# voltage_conditioning.net
KiCad netlist of a schematic drawn in Altium Designer
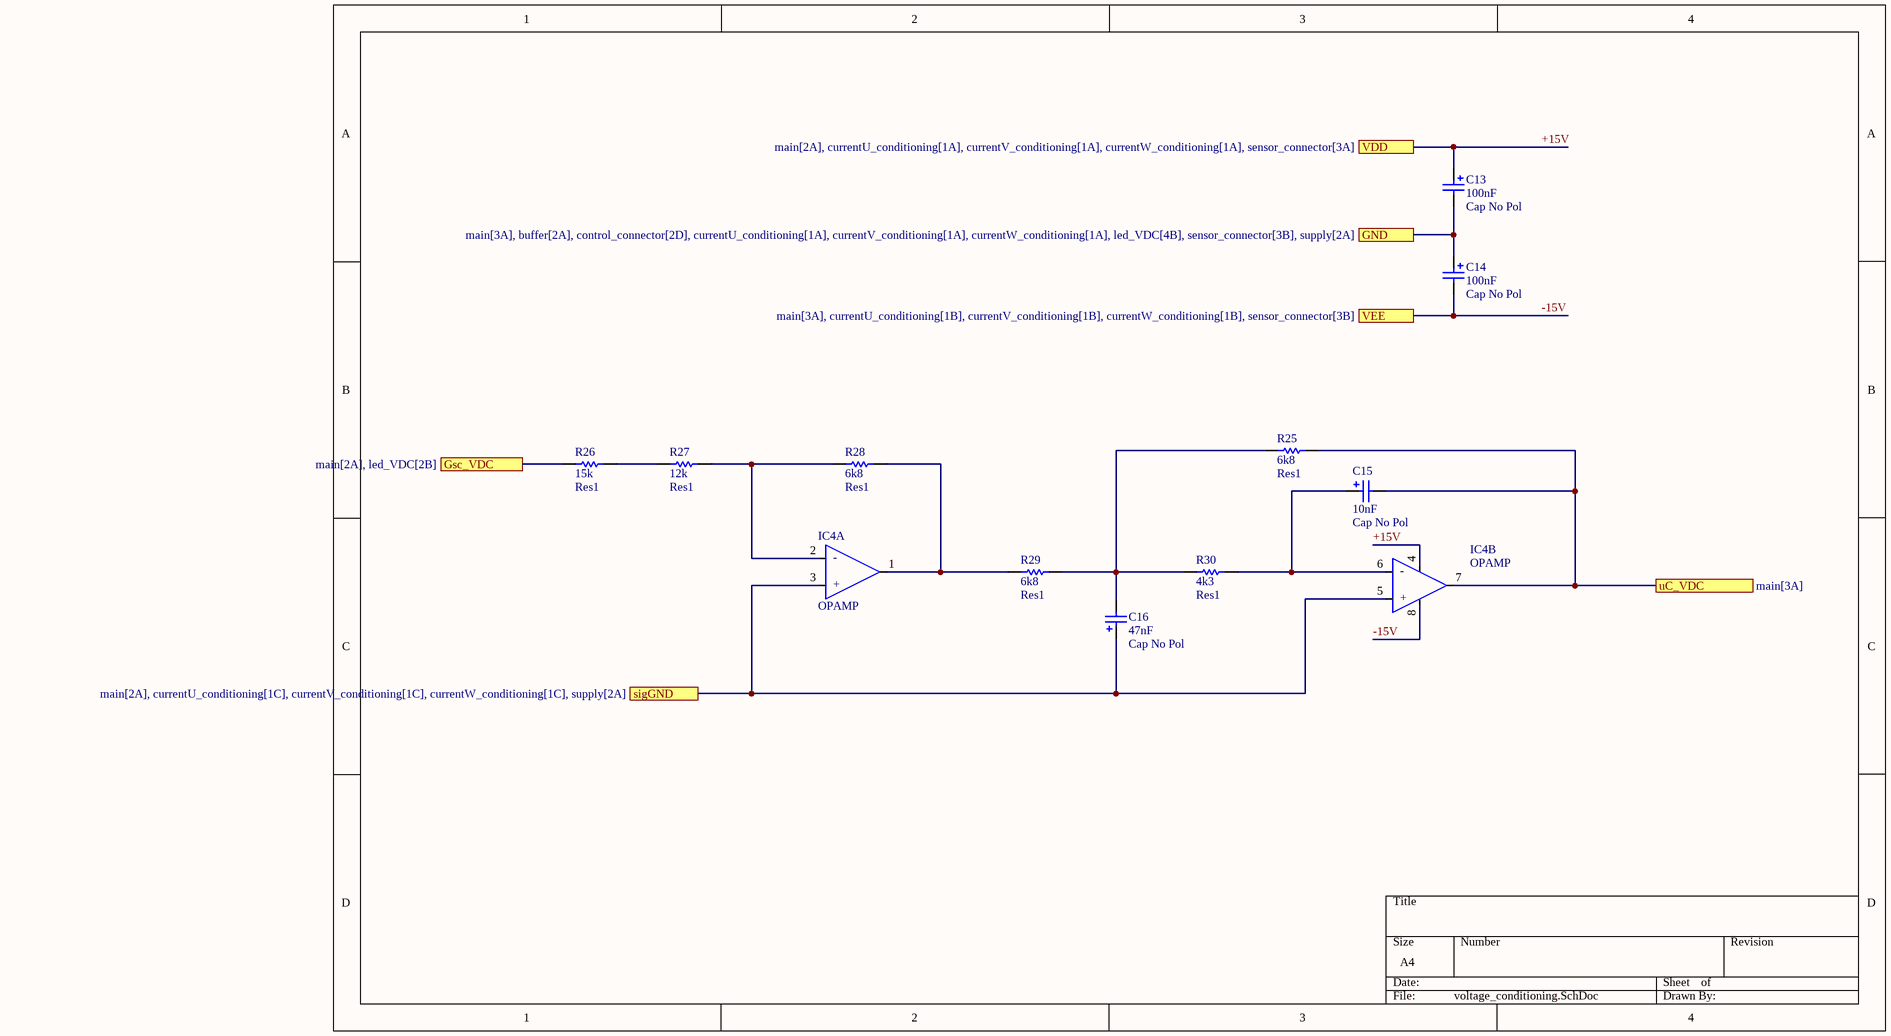
[diagram p0: voltage_conditioning.SchDoc]

(export (version "E")
  (design (tool "Eeschema 10.0.6"))
  (components
    (comp (ref "C13")
      (value "Cap No Pol")
      (footprint "RAD-0.1")
      (description "Polarized Capacitor (Radial)")
      (fields (field (name "ALTIUM_VALUE") "100nF") (field (name "PUBLISHER") "Altium Limited"))
      (libsource (lib "LABSTEPS_Project") (part "Cap No Pol"))
    )
    (comp (ref "C14")
      (value "Cap No Pol")
      (footprint "RAD-0.1")
      (description "Polarized Capacitor (Radial)")
      (fields (field (name "ALTIUM_VALUE") "100nF") (field (name "PUBLISHER") "Altium Limited"))
      (libsource (lib "LABSTEPS_Project") (part "Cap No Pol"))
    )
    (comp (ref "C15")
      (value "Cap No Pol")
      (footprint "RAD-0.1")
      (description "Polarized Capacitor (Radial)")
      (fields (field (name "ALTIUM_VALUE") "10nF") (field (name "PUBLISHER") "Altium Limited"))
      (libsource (lib "LABSTEPS_Project") (part "Cap No Pol"))
    )
    (comp (ref "C16")
      (value "Cap No Pol")
      (footprint "RAD-0.1")
      (description "Polarized Capacitor (Radial)")
      (fields (field (name "ALTIUM_VALUE") "47nF") (field (name "PUBLISHER") "Altium Limited"))
      (libsource (lib "LABSTEPS_Project") (part "Cap No Pol"))
    )
    (comp (ref "IC4")
      (value "OPAMP")
      (footprint "DIP-8")
      (description "ADTL082")
      (libsource (lib "LABSTEPS_Project") (part "ADTL082"))
    )
    (comp (ref "R25")
      (value "Res1")
      (footprint "AXIAL-0.3")
      (description "Resistor")
      (fields (field (name "ALTIUM_VALUE") "6k8") (field (name "PUBLISHER") "Altium Limited"))
      (libsource (lib "LABSTEPS_Project") (part "Res1"))
    )
    (comp (ref "R26")
      (value "Res1")
      (footprint "AXIAL-0.3")
      (description "Resistor")
      (fields (field (name "ALTIUM_VALUE") "15k") (field (name "PUBLISHER") "Altium Limited"))
      (libsource (lib "LABSTEPS_Project") (part "Res1"))
    )
    (comp (ref "R27")
      (value "Res1")
      (footprint "AXIAL-0.3")
      (description "Resistor")
      (fields (field (name "ALTIUM_VALUE") "12k") (field (name "PUBLISHER") "Altium Limited"))
      (libsource (lib "LABSTEPS_Project") (part "Res1"))
    )
    (comp (ref "R28")
      (value "Res1")
      (footprint "AXIAL-0.3")
      (description "Resistor")
      (fields (field (name "ALTIUM_VALUE") "6k8") (field (name "PUBLISHER") "Altium Limited"))
      (libsource (lib "LABSTEPS_Project") (part "Res1"))
    )
    (comp (ref "R29")
      (value "Res1")
      (footprint "AXIAL-0.3")
      (description "Resistor")
      (fields (field (name "ALTIUM_VALUE") "6k8") (field (name "PUBLISHER") "Altium Limited"))
      (libsource (lib "LABSTEPS_Project") (part "Res1"))
    )
    (comp (ref "R30")
      (value "Res1")
      (footprint "AXIAL-0.3")
      (description "Resistor")
      (fields (field (name "ALTIUM_VALUE") "4k3") (field (name "PUBLISHER") "Altium Limited"))
      (libsource (lib "LABSTEPS_Project") (part "Res1"))
    )
  )
  (nets
    (net (code "1") (name "/+15V") (class "Default")
      (node (ref "C13") (pin "1") (pinfunction "1_1") (pintype "passive"))
      (node (ref "IC4") (pin "4") (pinfunction "-V_4") (pintype "passive"))
    )
    (net (code "2") (name "/-15V") (class "Default")
      (node (ref "C14") (pin "2") (pinfunction "2_2") (pintype "passive"))
      (node (ref "IC4") (pin "8") (pinfunction "V+_8") (pintype "passive"))
    )
    (net (code "3") (name "/GND") (class "Default")
      (node (ref "C13") (pin "2") (pinfunction "2_2") (pintype "passive"))
      (node (ref "C14") (pin "1") (pinfunction "1_1") (pintype "passive"))
    )
    (net (code "4") (name "/Gsc_VDC") (class "Default")
      (node (ref "R26") (pin "1") (pinfunction "1_1") (pintype "passive"))
    )
    (net (code "5") (name "/sigGND") (class "Default")
      (node (ref "C16") (pin "1") (pinfunction "1_1") (pintype "passive"))
      (node (ref "IC4") (pin "3") (pinfunction "IN_A_+_3") (pintype "passive"))
      (node (ref "IC4") (pin "5") (pinfunction "IN_B_+_5") (pintype "passive"))
    )
    (net (code "6") (name "/uC_VDC") (class "Default")
      (node (ref "C15") (pin "2") (pinfunction "2_2") (pintype "passive"))
      (node (ref "IC4") (pin "7") (pinfunction "OUT_B_7") (pintype "passive"))
      (node (ref "R25") (pin "2") (pinfunction "2_2") (pintype "passive"))
    )
    (net (code "7") (name "Net-(C16-Pad2)") (class "Default")
      (node (ref "C16") (pin "2") (pinfunction "2_2") (pintype "passive"))
      (node (ref "R25") (pin "1") (pinfunction "1_1") (pintype "passive"))
      (node (ref "R29") (pin "2") (pinfunction "2_2") (pintype "passive"))
      (node (ref "R30") (pin "1") (pinfunction "1_1") (pintype "passive"))
    )
    (net (code "8") (name "Net-(IC4A-IN_A_-)") (class "Default")
      (node (ref "IC4") (pin "2") (pinfunction "IN_A_-_2") (pintype "passive"))
      (node (ref "R27") (pin "2") (pinfunction "2_2") (pintype "passive"))
      (node (ref "R28") (pin "1") (pinfunction "1_1") (pintype "passive"))
    )
    (net (code "9") (name "Net-(IC4A-OUT_A)") (class "Default")
      (node (ref "IC4") (pin "1") (pinfunction "OUT_A_1") (pintype "passive"))
      (node (ref "R28") (pin "2") (pinfunction "2_2") (pintype "passive"))
      (node (ref "R29") (pin "1") (pinfunction "1_1") (pintype "passive"))
    )
    (net (code "10") (name "Net-(IC4B-IN_B_-)") (class "Default")
      (node (ref "C15") (pin "1") (pinfunction "1_1") (pintype "passive"))
      (node (ref "IC4") (pin "6") (pinfunction "IN_B_-_6") (pintype "passive"))
      (node (ref "R30") (pin "2") (pinfunction "2_2") (pintype "passive"))
    )
    (net (code "11") (name "Net-(R26-Pad2)") (class "Default")
      (node (ref "R26") (pin "2") (pinfunction "2_2") (pintype "passive"))
      (node (ref "R27") (pin "1") (pinfunction "1_1") (pintype "passive"))
    )
  )
)
